# Lixieuhr-Segment.net
KiCad netlist of a schematic drawn in EAGLE
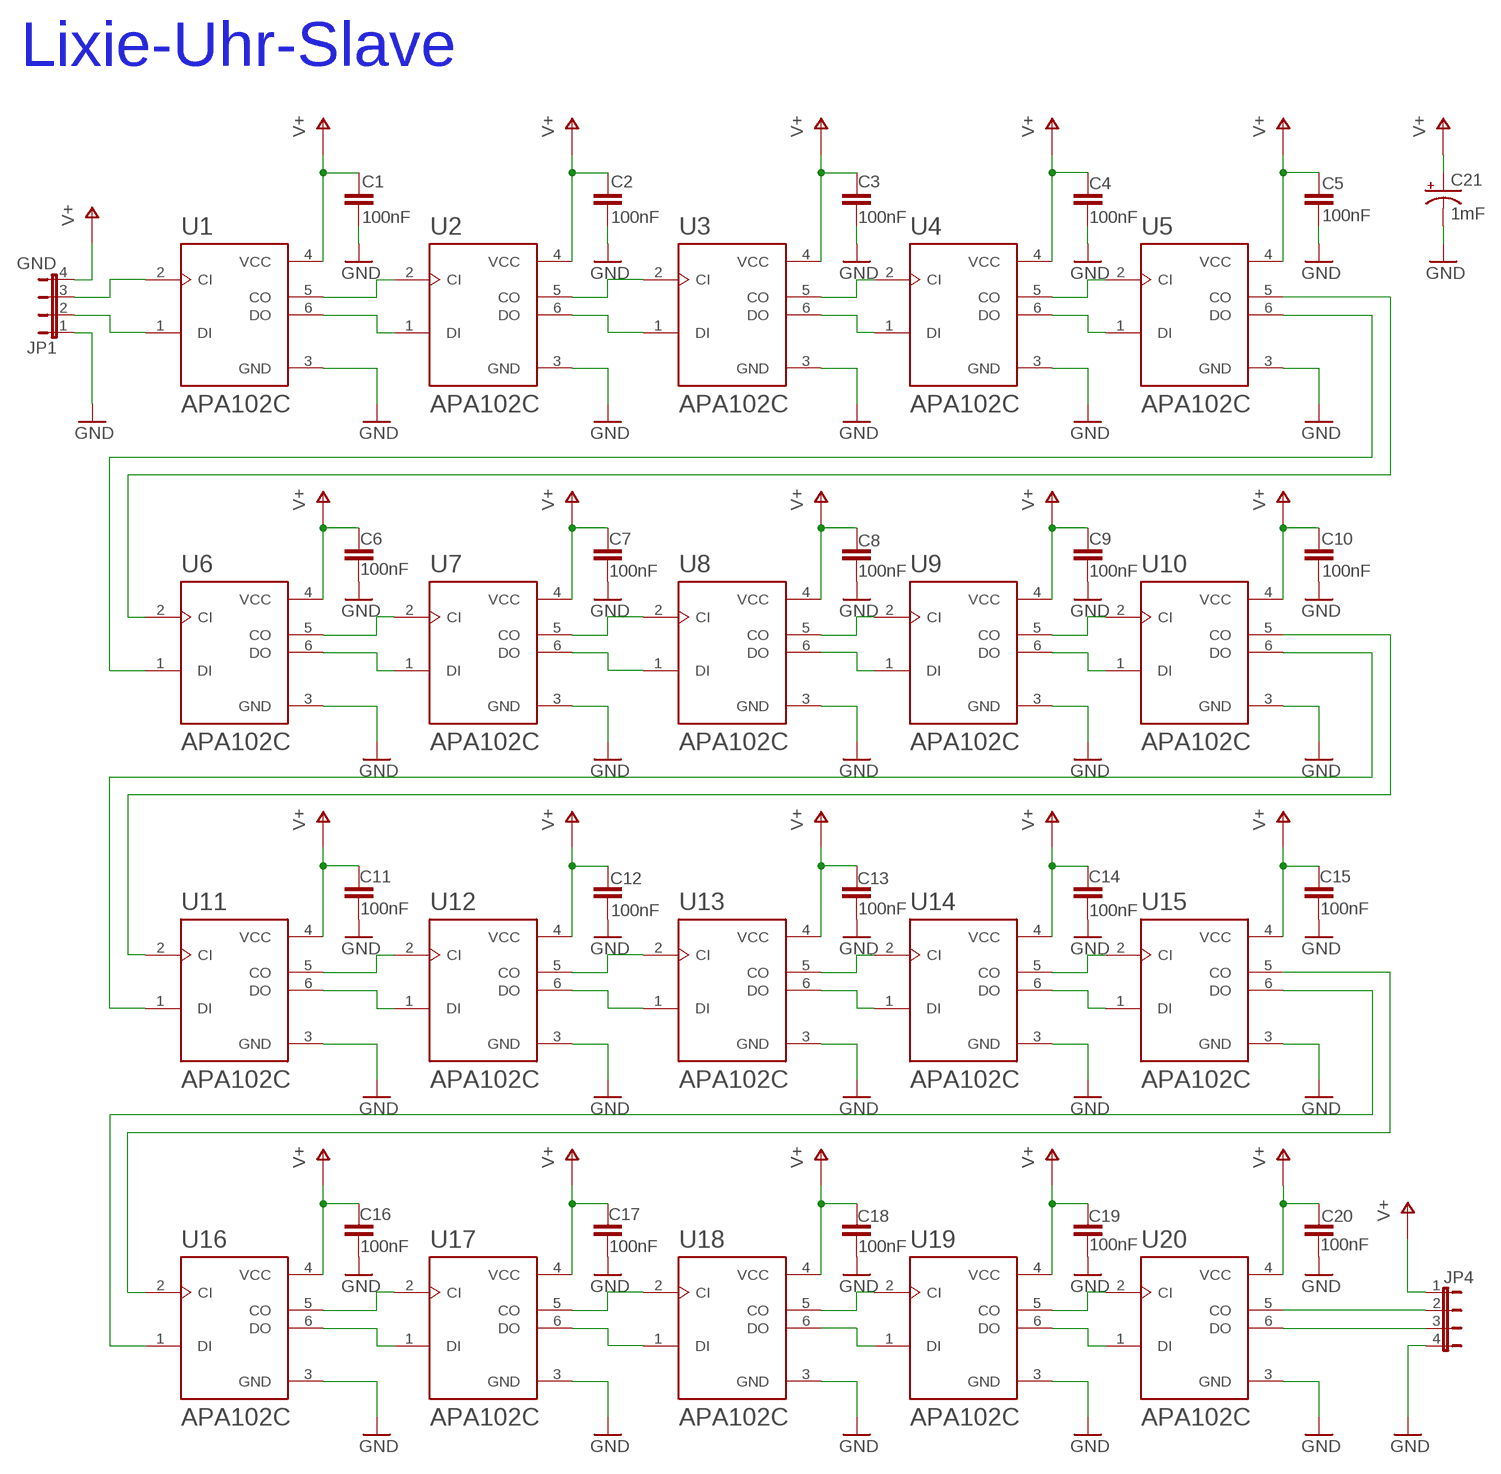
[diagram p0: schematic, sheet 1]

(export (version "E")
  (design (tool "Eeschema 10.0.6"))
  (components
    (comp (ref "C1")
      (value "100nF")
      (footprint "eagle-import:C0805")
      (libsource (lib "eagle-import") (part "C-0805"))
    )
    (comp (ref "C2")
      (value "100nF")
      (footprint "eagle-import:C0805")
      (libsource (lib "eagle-import") (part "C-0805"))
    )
    (comp (ref "C3")
      (value "100nF")
      (footprint "eagle-import:C0805")
      (libsource (lib "eagle-import") (part "C-0805"))
    )
    (comp (ref "C4")
      (value "100nF")
      (footprint "eagle-import:C0805")
      (libsource (lib "eagle-import") (part "C-0805"))
    )
    (comp (ref "C5")
      (value "100nF")
      (footprint "eagle-import:C0805")
      (libsource (lib "eagle-import") (part "C-0805"))
    )
    (comp (ref "C6")
      (value "100nF")
      (footprint "eagle-import:C0805")
      (libsource (lib "eagle-import") (part "C-0805"))
    )
    (comp (ref "C7")
      (value "100nF")
      (footprint "eagle-import:C0805")
      (libsource (lib "eagle-import") (part "C-0805"))
    )
    (comp (ref "C8")
      (value "100nF")
      (footprint "eagle-import:C0805")
      (libsource (lib "eagle-import") (part "C-0805"))
    )
    (comp (ref "C9")
      (value "100nF")
      (footprint "eagle-import:C0805")
      (libsource (lib "eagle-import") (part "C-0805"))
    )
    (comp (ref "C10")
      (value "100nF")
      (footprint "eagle-import:C0805")
      (libsource (lib "eagle-import") (part "C-0805"))
    )
    (comp (ref "C11")
      (value "100nF")
      (footprint "eagle-import:C0805")
      (libsource (lib "eagle-import") (part "C-0805"))
    )
    (comp (ref "C12")
      (value "100nF")
      (footprint "eagle-import:C0805")
      (libsource (lib "eagle-import") (part "C-0805"))
    )
    (comp (ref "C13")
      (value "100nF")
      (footprint "eagle-import:C0805")
      (libsource (lib "eagle-import") (part "C-0805"))
    )
    (comp (ref "C14")
      (value "100nF")
      (footprint "eagle-import:C0805")
      (libsource (lib "eagle-import") (part "C-0805"))
    )
    (comp (ref "C15")
      (value "100nF")
      (footprint "eagle-import:C0805")
      (libsource (lib "eagle-import") (part "C-0805"))
    )
    (comp (ref "C16")
      (value "100nF")
      (footprint "eagle-import:C0805")
      (libsource (lib "eagle-import") (part "C-0805"))
    )
    (comp (ref "C17")
      (value "100nF")
      (footprint "eagle-import:C0805")
      (libsource (lib "eagle-import") (part "C-0805"))
    )
    (comp (ref "C18")
      (value "100nF")
      (footprint "eagle-import:C0805")
      (libsource (lib "eagle-import") (part "C-0805"))
    )
    (comp (ref "C19")
      (value "100nF")
      (footprint "eagle-import:C0805")
      (libsource (lib "eagle-import") (part "C-0805"))
    )
    (comp (ref "C20")
      (value "100nF")
      (footprint "eagle-import:C0805")
      (libsource (lib "eagle-import") (part "C-0805"))
    )
    (comp (ref "C21")
      (value "1mF")
      (footprint "eagle-import:E3,5-8")
      (libsource (lib "eagle-import") (part "CPOL-USE3.5-8"))
    )
    (comp (ref "JP1")
      (value "GND")
      (footprint "eagle-import:JP4")
      (libsource (lib "eagle-import") (part "JP4E"))
    )
    (comp (ref "JP4")
      (value "JP4E")
      (footprint "eagle-import:JP4")
      (libsource (lib "eagle-import") (part "JP4E"))
    )
    (comp (ref "U1")
      (value "APA102C")
      (footprint "eagle-import:SON160P500X500X140-6N")
      (fields (field (name "MF") "Shiji Lighting"))
      (libsource (lib "eagle-import") (part "APA102C"))
    )
    (comp (ref "U2")
      (value "APA102C")
      (footprint "eagle-import:SON160P500X500X140-6N")
      (fields (field (name "MF") "Shiji Lighting"))
      (libsource (lib "eagle-import") (part "APA102C"))
    )
    (comp (ref "U3")
      (value "APA102C")
      (footprint "eagle-import:SON160P500X500X140-6N")
      (fields (field (name "MF") "Shiji Lighting"))
      (libsource (lib "eagle-import") (part "APA102C"))
    )
    (comp (ref "U4")
      (value "APA102C")
      (footprint "eagle-import:SON160P500X500X140-6N")
      (fields (field (name "MF") "Shiji Lighting"))
      (libsource (lib "eagle-import") (part "APA102C"))
    )
    (comp (ref "U5")
      (value "APA102C")
      (footprint "eagle-import:SON160P500X500X140-6N")
      (fields (field (name "MF") "Shiji Lighting"))
      (libsource (lib "eagle-import") (part "APA102C"))
    )
    (comp (ref "U6")
      (value "APA102C")
      (footprint "eagle-import:SON160P500X500X140-6N")
      (fields (field (name "MF") "Shiji Lighting"))
      (libsource (lib "eagle-import") (part "APA102C"))
    )
    (comp (ref "U7")
      (value "APA102C")
      (footprint "eagle-import:SON160P500X500X140-6N")
      (fields (field (name "MF") "Shiji Lighting"))
      (libsource (lib "eagle-import") (part "APA102C"))
    )
    (comp (ref "U8")
      (value "APA102C")
      (footprint "eagle-import:SON160P500X500X140-6N")
      (fields (field (name "MF") "Shiji Lighting"))
      (libsource (lib "eagle-import") (part "APA102C"))
    )
    (comp (ref "U9")
      (value "APA102C")
      (footprint "eagle-import:SON160P500X500X140-6N")
      (fields (field (name "MF") "Shiji Lighting"))
      (libsource (lib "eagle-import") (part "APA102C"))
    )
    (comp (ref "U10")
      (value "APA102C")
      (footprint "eagle-import:SON160P500X500X140-6N")
      (fields (field (name "MF") "Shiji Lighting"))
      (libsource (lib "eagle-import") (part "APA102C"))
    )
    (comp (ref "U11")
      (value "APA102C")
      (footprint "eagle-import:SON160P500X500X140-6N")
      (fields (field (name "MF") "Shiji Lighting"))
      (libsource (lib "eagle-import") (part "APA102C"))
    )
    (comp (ref "U12")
      (value "APA102C")
      (footprint "eagle-import:SON160P500X500X140-6N")
      (fields (field (name "MF") "Shiji Lighting"))
      (libsource (lib "eagle-import") (part "APA102C"))
    )
    (comp (ref "U13")
      (value "APA102C")
      (footprint "eagle-import:SON160P500X500X140-6N")
      (fields (field (name "MF") "Shiji Lighting"))
      (libsource (lib "eagle-import") (part "APA102C"))
    )
    (comp (ref "U14")
      (value "APA102C")
      (footprint "eagle-import:SON160P500X500X140-6N")
      (fields (field (name "MF") "Shiji Lighting"))
      (libsource (lib "eagle-import") (part "APA102C"))
    )
    (comp (ref "U15")
      (value "APA102C")
      (footprint "eagle-import:SON160P500X500X140-6N")
      (fields (field (name "MF") "Shiji Lighting"))
      (libsource (lib "eagle-import") (part "APA102C"))
    )
    (comp (ref "U16")
      (value "APA102C")
      (footprint "eagle-import:SON160P500X500X140-6N")
      (fields (field (name "MF") "Shiji Lighting"))
      (libsource (lib "eagle-import") (part "APA102C"))
    )
    (comp (ref "U17")
      (value "APA102C")
      (footprint "eagle-import:SON160P500X500X140-6N")
      (fields (field (name "MF") "Shiji Lighting"))
      (libsource (lib "eagle-import") (part "APA102C"))
    )
    (comp (ref "U18")
      (value "APA102C")
      (footprint "eagle-import:SON160P500X500X140-6N")
      (fields (field (name "MF") "Shiji Lighting"))
      (libsource (lib "eagle-import") (part "APA102C"))
    )
    (comp (ref "U19")
      (value "APA102C")
      (footprint "eagle-import:SON160P500X500X140-6N")
      (fields (field (name "MF") "Shiji Lighting"))
      (libsource (lib "eagle-import") (part "APA102C"))
    )
    (comp (ref "U20")
      (value "APA102C")
      (footprint "eagle-import:SON160P500X500X140-6N")
      (fields (field (name "MF") "Shiji Lighting"))
      (libsource (lib "eagle-import") (part "APA102C"))
    )
  )
  (nets
    (net (code "1") (name "GND") (class "Default")
      (node (ref "C1") (pin "1") (pinfunction "1_1") (pintype "passive"))
      (node (ref "C10") (pin "1") (pinfunction "1_1") (pintype "passive"))
      (node (ref "C11") (pin "1") (pinfunction "1_1") (pintype "passive"))
      (node (ref "C12") (pin "1") (pinfunction "1_1") (pintype "passive"))
      (node (ref "C13") (pin "1") (pinfunction "1_1") (pintype "passive"))
      (node (ref "C14") (pin "1") (pinfunction "1_1") (pintype "passive"))
      (node (ref "C15") (pin "1") (pinfunction "1_1") (pintype "passive"))
      (node (ref "C16") (pin "1") (pinfunction "1_1") (pintype "passive"))
      (node (ref "C17") (pin "1") (pinfunction "1_1") (pintype "passive"))
      (node (ref "C18") (pin "1") (pinfunction "1_1") (pintype "passive"))
      (node (ref "C19") (pin "1") (pinfunction "1_1") (pintype "passive"))
      (node (ref "C2") (pin "1") (pinfunction "1_1") (pintype "passive"))
      (node (ref "C20") (pin "1") (pinfunction "1_1") (pintype "passive"))
      (node (ref "C21") (pin "-") (pinfunction "-_-") (pintype "passive"))
      (node (ref "C3") (pin "1") (pinfunction "1_1") (pintype "passive"))
      (node (ref "C4") (pin "1") (pinfunction "1_1") (pintype "passive"))
      (node (ref "C5") (pin "1") (pinfunction "1_1") (pintype "passive"))
      (node (ref "C6") (pin "1") (pinfunction "1_1") (pintype "passive"))
      (node (ref "C7") (pin "1") (pinfunction "1_1") (pintype "passive"))
      (node (ref "C8") (pin "1") (pinfunction "1_1") (pintype "passive"))
      (node (ref "C9") (pin "1") (pinfunction "1_1") (pintype "passive"))
      (node (ref "JP1") (pin "1") (pinfunction "1_1") (pintype "passive"))
      (node (ref "JP4") (pin "4") (pinfunction "4_4") (pintype "passive"))
      (node (ref "U1") (pin "3") (pinfunction "GND_3") (pintype "power_in"))
      (node (ref "U10") (pin "3") (pinfunction "GND_3") (pintype "power_in"))
      (node (ref "U11") (pin "3") (pinfunction "GND_3") (pintype "power_in"))
      (node (ref "U12") (pin "3") (pinfunction "GND_3") (pintype "power_in"))
      (node (ref "U13") (pin "3") (pinfunction "GND_3") (pintype "power_in"))
      (node (ref "U14") (pin "3") (pinfunction "GND_3") (pintype "power_in"))
      (node (ref "U15") (pin "3") (pinfunction "GND_3") (pintype "power_in"))
      (node (ref "U16") (pin "3") (pinfunction "GND_3") (pintype "power_in"))
      (node (ref "U17") (pin "3") (pinfunction "GND_3") (pintype "power_in"))
      (node (ref "U18") (pin "3") (pinfunction "GND_3") (pintype "power_in"))
      (node (ref "U19") (pin "3") (pinfunction "GND_3") (pintype "power_in"))
      (node (ref "U2") (pin "3") (pinfunction "GND_3") (pintype "power_in"))
      (node (ref "U20") (pin "3") (pinfunction "GND_3") (pintype "power_in"))
      (node (ref "U3") (pin "3") (pinfunction "GND_3") (pintype "power_in"))
      (node (ref "U4") (pin "3") (pinfunction "GND_3") (pintype "power_in"))
      (node (ref "U5") (pin "3") (pinfunction "GND_3") (pintype "power_in"))
      (node (ref "U6") (pin "3") (pinfunction "GND_3") (pintype "power_in"))
      (node (ref "U7") (pin "3") (pinfunction "GND_3") (pintype "power_in"))
      (node (ref "U8") (pin "3") (pinfunction "GND_3") (pintype "power_in"))
      (node (ref "U9") (pin "3") (pinfunction "GND_3") (pintype "power_in"))
    )
    (net (code "2") (name "Net-(U1-CI)") (class "Default")
      (node (ref "JP1") (pin "3") (pinfunction "3_3") (pintype "passive"))
      (node (ref "U1") (pin "2") (pinfunction "CI_2") (pintype "input"))
    )
    (net (code "3") (name "Net-(U1-CO)") (class "Default")
      (node (ref "U1") (pin "5") (pinfunction "CO_5") (pintype "output"))
      (node (ref "U2") (pin "2") (pinfunction "CI_2") (pintype "input"))
    )
    (net (code "4") (name "Net-(U1-DI)") (class "Default")
      (node (ref "JP1") (pin "2") (pinfunction "2_2") (pintype "passive"))
      (node (ref "U1") (pin "1") (pinfunction "DI_1") (pintype "input"))
    )
    (net (code "5") (name "Net-(U1-DO)") (class "Default")
      (node (ref "U1") (pin "6") (pinfunction "DO_6") (pintype "output"))
      (node (ref "U2") (pin "1") (pinfunction "DI_1") (pintype "input"))
    )
    (net (code "6") (name "Net-(U2-CO)") (class "Default")
      (node (ref "U2") (pin "5") (pinfunction "CO_5") (pintype "output"))
      (node (ref "U3") (pin "2") (pinfunction "CI_2") (pintype "input"))
    )
    (net (code "7") (name "Net-(U2-DO)") (class "Default")
      (node (ref "U2") (pin "6") (pinfunction "DO_6") (pintype "output"))
      (node (ref "U3") (pin "1") (pinfunction "DI_1") (pintype "input"))
    )
    (net (code "8") (name "Net-(U3-CO)") (class "Default")
      (node (ref "U3") (pin "5") (pinfunction "CO_5") (pintype "output"))
      (node (ref "U4") (pin "2") (pinfunction "CI_2") (pintype "input"))
    )
    (net (code "9") (name "Net-(U3-DO)") (class "Default")
      (node (ref "U3") (pin "6") (pinfunction "DO_6") (pintype "output"))
      (node (ref "U4") (pin "1") (pinfunction "DI_1") (pintype "input"))
    )
    (net (code "10") (name "Net-(U4-CO)") (class "Default")
      (node (ref "U4") (pin "5") (pinfunction "CO_5") (pintype "output"))
      (node (ref "U5") (pin "2") (pinfunction "CI_2") (pintype "input"))
    )
    (net (code "11") (name "Net-(U4-DO)") (class "Default")
      (node (ref "U4") (pin "6") (pinfunction "DO_6") (pintype "output"))
      (node (ref "U5") (pin "1") (pinfunction "DI_1") (pintype "input"))
    )
    (net (code "12") (name "Net-(U5-CO)") (class "Default")
      (node (ref "U5") (pin "5") (pinfunction "CO_5") (pintype "output"))
      (node (ref "U6") (pin "2") (pinfunction "CI_2") (pintype "input"))
    )
    (net (code "13") (name "Net-(U5-DO)") (class "Default")
      (node (ref "U5") (pin "6") (pinfunction "DO_6") (pintype "output"))
      (node (ref "U6") (pin "1") (pinfunction "DI_1") (pintype "input"))
    )
    (net (code "14") (name "Net-(U6-CO)") (class "Default")
      (node (ref "U6") (pin "5") (pinfunction "CO_5") (pintype "output"))
      (node (ref "U7") (pin "2") (pinfunction "CI_2") (pintype "input"))
    )
    (net (code "15") (name "Net-(U6-DO)") (class "Default")
      (node (ref "U6") (pin "6") (pinfunction "DO_6") (pintype "output"))
      (node (ref "U7") (pin "1") (pinfunction "DI_1") (pintype "input"))
    )
    (net (code "16") (name "Net-(U7-CO)") (class "Default")
      (node (ref "U7") (pin "5") (pinfunction "CO_5") (pintype "output"))
      (node (ref "U8") (pin "2") (pinfunction "CI_2") (pintype "input"))
    )
    (net (code "17") (name "Net-(U7-DO)") (class "Default")
      (node (ref "U7") (pin "6") (pinfunction "DO_6") (pintype "output"))
      (node (ref "U8") (pin "1") (pinfunction "DI_1") (pintype "input"))
    )
    (net (code "18") (name "Net-(U8-CO)") (class "Default")
      (node (ref "U8") (pin "5") (pinfunction "CO_5") (pintype "output"))
      (node (ref "U9") (pin "2") (pinfunction "CI_2") (pintype "input"))
    )
    (net (code "19") (name "Net-(U8-DO)") (class "Default")
      (node (ref "U8") (pin "6") (pinfunction "DO_6") (pintype "output"))
      (node (ref "U9") (pin "1") (pinfunction "DI_1") (pintype "input"))
    )
    (net (code "20") (name "Net-(U10-CI)") (class "Default")
      (node (ref "U10") (pin "2") (pinfunction "CI_2") (pintype "input"))
      (node (ref "U9") (pin "5") (pinfunction "CO_5") (pintype "output"))
    )
    (net (code "21") (name "Net-(U10-CO)") (class "Default")
      (node (ref "U10") (pin "5") (pinfunction "CO_5") (pintype "output"))
      (node (ref "U11") (pin "2") (pinfunction "CI_2") (pintype "input"))
    )
    (net (code "22") (name "Net-(U10-DI)") (class "Default")
      (node (ref "U10") (pin "1") (pinfunction "DI_1") (pintype "input"))
      (node (ref "U9") (pin "6") (pinfunction "DO_6") (pintype "output"))
    )
    (net (code "23") (name "Net-(U10-DO)") (class "Default")
      (node (ref "U10") (pin "6") (pinfunction "DO_6") (pintype "output"))
      (node (ref "U11") (pin "1") (pinfunction "DI_1") (pintype "input"))
    )
    (net (code "24") (name "Net-(U11-CO)") (class "Default")
      (node (ref "U11") (pin "5") (pinfunction "CO_5") (pintype "output"))
      (node (ref "U12") (pin "2") (pinfunction "CI_2") (pintype "input"))
    )
    (net (code "25") (name "Net-(U11-DO)") (class "Default")
      (node (ref "U11") (pin "6") (pinfunction "DO_6") (pintype "output"))
      (node (ref "U12") (pin "1") (pinfunction "DI_1") (pintype "input"))
    )
    (net (code "26") (name "Net-(U12-CO)") (class "Default")
      (node (ref "U12") (pin "5") (pinfunction "CO_5") (pintype "output"))
      (node (ref "U13") (pin "2") (pinfunction "CI_2") (pintype "input"))
    )
    (net (code "27") (name "Net-(U12-DO)") (class "Default")
      (node (ref "U12") (pin "6") (pinfunction "DO_6") (pintype "output"))
      (node (ref "U13") (pin "1") (pinfunction "DI_1") (pintype "input"))
    )
    (net (code "28") (name "Net-(U13-CO)") (class "Default")
      (node (ref "U13") (pin "5") (pinfunction "CO_5") (pintype "output"))
      (node (ref "U14") (pin "2") (pinfunction "CI_2") (pintype "input"))
    )
    (net (code "29") (name "Net-(U13-DO)") (class "Default")
      (node (ref "U13") (pin "6") (pinfunction "DO_6") (pintype "output"))
      (node (ref "U14") (pin "1") (pinfunction "DI_1") (pintype "input"))
    )
    (net (code "30") (name "Net-(U14-CO)") (class "Default")
      (node (ref "U14") (pin "5") (pinfunction "CO_5") (pintype "output"))
      (node (ref "U15") (pin "2") (pinfunction "CI_2") (pintype "input"))
    )
    (net (code "31") (name "Net-(U14-DO)") (class "Default")
      (node (ref "U14") (pin "6") (pinfunction "DO_6") (pintype "output"))
      (node (ref "U15") (pin "1") (pinfunction "DI_1") (pintype "input"))
    )
    (net (code "32") (name "Net-(U15-CO)") (class "Default")
      (node (ref "U15") (pin "5") (pinfunction "CO_5") (pintype "output"))
      (node (ref "U16") (pin "2") (pinfunction "CI_2") (pintype "input"))
    )
    (net (code "33") (name "Net-(U15-DO)") (class "Default")
      (node (ref "U15") (pin "6") (pinfunction "DO_6") (pintype "output"))
      (node (ref "U16") (pin "1") (pinfunction "DI_1") (pintype "input"))
    )
    (net (code "34") (name "Net-(U16-CO)") (class "Default")
      (node (ref "U16") (pin "5") (pinfunction "CO_5") (pintype "output"))
      (node (ref "U17") (pin "2") (pinfunction "CI_2") (pintype "input"))
    )
    (net (code "35") (name "Net-(U16-DO)") (class "Default")
      (node (ref "U16") (pin "6") (pinfunction "DO_6") (pintype "output"))
      (node (ref "U17") (pin "1") (pinfunction "DI_1") (pintype "input"))
    )
    (net (code "36") (name "Net-(U17-CO)") (class "Default")
      (node (ref "U17") (pin "5") (pinfunction "CO_5") (pintype "output"))
      (node (ref "U18") (pin "2") (pinfunction "CI_2") (pintype "input"))
    )
    (net (code "37") (name "Net-(U17-DO)") (class "Default")
      (node (ref "U17") (pin "6") (pinfunction "DO_6") (pintype "output"))
      (node (ref "U18") (pin "1") (pinfunction "DI_1") (pintype "input"))
    )
    (net (code "38") (name "Net-(U18-CO)") (class "Default")
      (node (ref "U18") (pin "5") (pinfunction "CO_5") (pintype "output"))
      (node (ref "U19") (pin "2") (pinfunction "CI_2") (pintype "input"))
    )
    (net (code "39") (name "Net-(U18-DO)") (class "Default")
      (node (ref "U18") (pin "6") (pinfunction "DO_6") (pintype "output"))
      (node (ref "U19") (pin "1") (pinfunction "DI_1") (pintype "input"))
    )
    (net (code "40") (name "Net-(U19-CO)") (class "Default")
      (node (ref "U19") (pin "5") (pinfunction "CO_5") (pintype "output"))
      (node (ref "U20") (pin "2") (pinfunction "CI_2") (pintype "input"))
    )
    (net (code "41") (name "Net-(U19-DO)") (class "Default")
      (node (ref "U19") (pin "6") (pinfunction "DO_6") (pintype "output"))
      (node (ref "U20") (pin "1") (pinfunction "DI_1") (pintype "input"))
    )
    (net (code "42") (name "Net-(U20-CO)") (class "Default")
      (node (ref "JP4") (pin "2") (pinfunction "2_2") (pintype "passive"))
      (node (ref "U20") (pin "5") (pinfunction "CO_5") (pintype "output"))
    )
    (net (code "43") (name "Net-(U20-DO)") (class "Default")
      (node (ref "JP4") (pin "3") (pinfunction "3_3") (pintype "passive"))
      (node (ref "U20") (pin "6") (pinfunction "DO_6") (pintype "output"))
    )
    (net (code "44") (name "V+") (class "Default")
      (node (ref "C1") (pin "2") (pinfunction "2_2") (pintype "passive"))
      (node (ref "C10") (pin "2") (pinfunction "2_2") (pintype "passive"))
      (node (ref "C11") (pin "2") (pinfunction "2_2") (pintype "passive"))
      (node (ref "C12") (pin "2") (pinfunction "2_2") (pintype "passive"))
      (node (ref "C13") (pin "2") (pinfunction "2_2") (pintype "passive"))
      (node (ref "C14") (pin "2") (pinfunction "2_2") (pintype "passive"))
      (node (ref "C15") (pin "2") (pinfunction "2_2") (pintype "passive"))
      (node (ref "C16") (pin "2") (pinfunction "2_2") (pintype "passive"))
      (node (ref "C17") (pin "2") (pinfunction "2_2") (pintype "passive"))
      (node (ref "C18") (pin "2") (pinfunction "2_2") (pintype "passive"))
      (node (ref "C19") (pin "2") (pinfunction "2_2") (pintype "passive"))
      (node (ref "C2") (pin "2") (pinfunction "2_2") (pintype "passive"))
      (node (ref "C20") (pin "2") (pinfunction "2_2") (pintype "passive"))
      (node (ref "C21") (pin "+") (pinfunction "+_+") (pintype "passive"))
      (node (ref "C3") (pin "2") (pinfunction "2_2") (pintype "passive"))
      (node (ref "C4") (pin "2") (pinfunction "2_2") (pintype "passive"))
      (node (ref "C5") (pin "2") (pinfunction "2_2") (pintype "passive"))
      (node (ref "C6") (pin "2") (pinfunction "2_2") (pintype "passive"))
      (node (ref "C7") (pin "2") (pinfunction "2_2") (pintype "passive"))
      (node (ref "C8") (pin "2") (pinfunction "2_2") (pintype "passive"))
      (node (ref "C9") (pin "2") (pinfunction "2_2") (pintype "passive"))
      (node (ref "JP1") (pin "4") (pinfunction "4_4") (pintype "passive"))
      (node (ref "JP4") (pin "1") (pinfunction "1_1") (pintype "passive"))
      (node (ref "U1") (pin "4") (pinfunction "VCC_4") (pintype "power_in"))
      (node (ref "U10") (pin "4") (pinfunction "VCC_4") (pintype "power_in"))
      (node (ref "U11") (pin "4") (pinfunction "VCC_4") (pintype "power_in"))
      (node (ref "U12") (pin "4") (pinfunction "VCC_4") (pintype "power_in"))
      (node (ref "U13") (pin "4") (pinfunction "VCC_4") (pintype "power_in"))
      (node (ref "U14") (pin "4") (pinfunction "VCC_4") (pintype "power_in"))
      (node (ref "U15") (pin "4") (pinfunction "VCC_4") (pintype "power_in"))
      (node (ref "U16") (pin "4") (pinfunction "VCC_4") (pintype "power_in"))
      (node (ref "U17") (pin "4") (pinfunction "VCC_4") (pintype "power_in"))
      (node (ref "U18") (pin "4") (pinfunction "VCC_4") (pintype "power_in"))
      (node (ref "U19") (pin "4") (pinfunction "VCC_4") (pintype "power_in"))
      (node (ref "U2") (pin "4") (pinfunction "VCC_4") (pintype "power_in"))
      (node (ref "U20") (pin "4") (pinfunction "VCC_4") (pintype "power_in"))
      (node (ref "U3") (pin "4") (pinfunction "VCC_4") (pintype "power_in"))
      (node (ref "U4") (pin "4") (pinfunction "VCC_4") (pintype "power_in"))
      (node (ref "U5") (pin "4") (pinfunction "VCC_4") (pintype "power_in"))
      (node (ref "U6") (pin "4") (pinfunction "VCC_4") (pintype "power_in"))
      (node (ref "U7") (pin "4") (pinfunction "VCC_4") (pintype "power_in"))
      (node (ref "U8") (pin "4") (pinfunction "VCC_4") (pintype "power_in"))
      (node (ref "U9") (pin "4") (pinfunction "VCC_4") (pintype "power_in"))
    )
  )
)
